# EncoderArm_PhotoReflector.net
KiCad netlist of a schematic drawn in Altium Designer
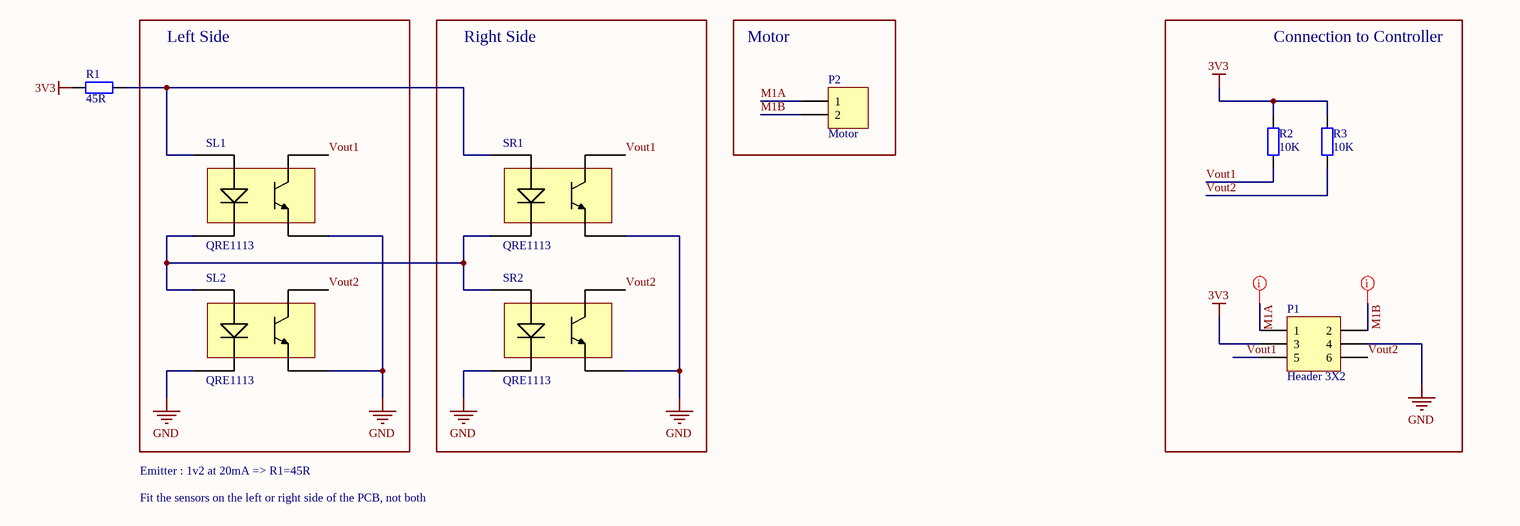
[diagram p0: EncoderArm_PhotoReflector.SchDoc]

(export (version "E")
  (design (tool "Eeschema 10.0.6"))
  (components
    (comp (ref "P1")
      (value "Header 3X2")
      (footprint "HDR2X3")
      (description "Header, 3-Pin, Dual row")
      (fields (field (name "PUBLISHER") "Altium Limited"))
      (libsource (lib "Miscellaneous Connectors") (part "Header 3X2"))
    )
    (comp (ref "P2")
      (value "Motor")
      (footprint "HDR1X2")
      (description "Header, 2-Pin")
      (fields (field (name "PUBLISHER") "Altium Limited"))
      (libsource (lib "Miscellaneous Connectors") (part "Header 2"))
    )
    (comp (ref "R1")
      (value "45R")
      (footprint "6-0805_M")
      (description "Resistor")
      (fields (field (name "Comment") "Res2") (field (name "PUBLISHER") "Altium Limited"))
      (libsource (lib "Miscellaneous Devices") (part "Res2"))
    )
    (comp (ref "R2")
      (value "10K")
      (footprint "6-0805_M")
      (description "Resistor")
      (fields (field (name "Comment") "Res2") (field (name "PUBLISHER") "Altium Limited"))
      (libsource (lib "") (part "Res2_1"))
    )
    (comp (ref "R3")
      (value "10K")
      (footprint "6-0805_M")
      (description "Resistor")
      (fields (field (name "Comment") "Res2") (field (name "PUBLISHER") "Altium Limited"))
      (libsource (lib "") (part "Res2_1"))
    )
    (comp (ref "SL1")
      (value "QRE1113")
      (footprint "QRE1113GR")
      (libsource (lib "PenguinPi_v2") (part "QRE1113"))
    )
    (comp (ref "SL2")
      (value "QRE1113")
      (footprint "QRE1113GR")
      (libsource (lib "PenguinPi_v2") (part "QRE1113"))
    )
    (comp (ref "SR1")
      (value "QRE1113")
      (footprint "QRE1113GR")
      (libsource (lib "PenguinPi_v2") (part "QRE1113"))
    )
    (comp (ref "SR2")
      (value "QRE1113")
      (footprint "QRE1113GR")
      (libsource (lib "PenguinPi_v2") (part "QRE1113"))
    )
  )
  (nets
    (net (code "1") (name "/M1A") (class "Default")
      (node (ref "P1") (pin "1") (pinfunction "1_1") (pintype "passive"))
      (node (ref "P2") (pin "1") (pinfunction "1_1") (pintype "passive"))
    )
    (net (code "2") (name "/M1B") (class "Default")
      (node (ref "P1") (pin "2") (pinfunction "2_2") (pintype "passive"))
      (node (ref "P2") (pin "2") (pinfunction "2_2") (pintype "passive"))
    )
    (net (code "3") (name "/Vout1") (class "Default")
      (node (ref "P1") (pin "5") (pinfunction "5_5") (pintype "passive"))
      (node (ref "R2") (pin "1") (pinfunction "1_1") (pintype "passive"))
      (node (ref "SL1") (pin "3") (pinfunction "C_3") (pintype "passive"))
      (node (ref "SR1") (pin "3") (pinfunction "C_3") (pintype "passive"))
    )
    (net (code "4") (name "/Vout2") (class "Default")
      (node (ref "P1") (pin "6") (pinfunction "6_6") (pintype "passive"))
      (node (ref "R3") (pin "1") (pinfunction "1_1") (pintype "passive"))
      (node (ref "SL2") (pin "3") (pinfunction "C_3") (pintype "passive"))
      (node (ref "SR2") (pin "3") (pinfunction "C_3") (pintype "passive"))
    )
    (net (code "5") (name "3V3") (class "Default")
      (node (ref "P1") (pin "3") (pinfunction "3_3") (pintype "passive"))
      (node (ref "R1") (pin "2") (pinfunction "2_2") (pintype "passive"))
      (node (ref "R2") (pin "2") (pinfunction "2_2") (pintype "passive"))
      (node (ref "R3") (pin "2") (pinfunction "2_2") (pintype "passive"))
    )
    (net (code "6") (name "GND") (class "Default")
      (node (ref "P1") (pin "4") (pinfunction "4_4") (pintype "passive"))
      (node (ref "SL1") (pin "4") (pinfunction "E_4") (pintype "passive"))
      (node (ref "SL2") (pin "2") (pinfunction "K_2") (pintype "passive"))
      (node (ref "SL2") (pin "4") (pinfunction "E_4") (pintype "passive"))
      (node (ref "SR1") (pin "4") (pinfunction "E_4") (pintype "passive"))
      (node (ref "SR2") (pin "2") (pinfunction "K_2") (pintype "passive"))
      (node (ref "SR2") (pin "4") (pinfunction "E_4") (pintype "passive"))
    )
    (net (code "7") (name "Net-(SL1-A)") (class "Default")
      (node (ref "R1") (pin "1") (pinfunction "1_1") (pintype "passive"))
      (node (ref "SL1") (pin "1") (pinfunction "A_1") (pintype "passive"))
      (node (ref "SR1") (pin "1") (pinfunction "A_1") (pintype "passive"))
    )
    (net (code "8") (name "Net-(SL1-K)") (class "Default")
      (node (ref "SL1") (pin "2") (pinfunction "K_2") (pintype "passive"))
      (node (ref "SL2") (pin "1") (pinfunction "A_1") (pintype "passive"))
      (node (ref "SR1") (pin "2") (pinfunction "K_2") (pintype "passive"))
      (node (ref "SR2") (pin "1") (pinfunction "A_1") (pintype "passive"))
    )
  )
)
